# SCH_SEGEMENTOS_MINUTERO_1.net
KiCad netlist of a schematic drawn in Altium Designer
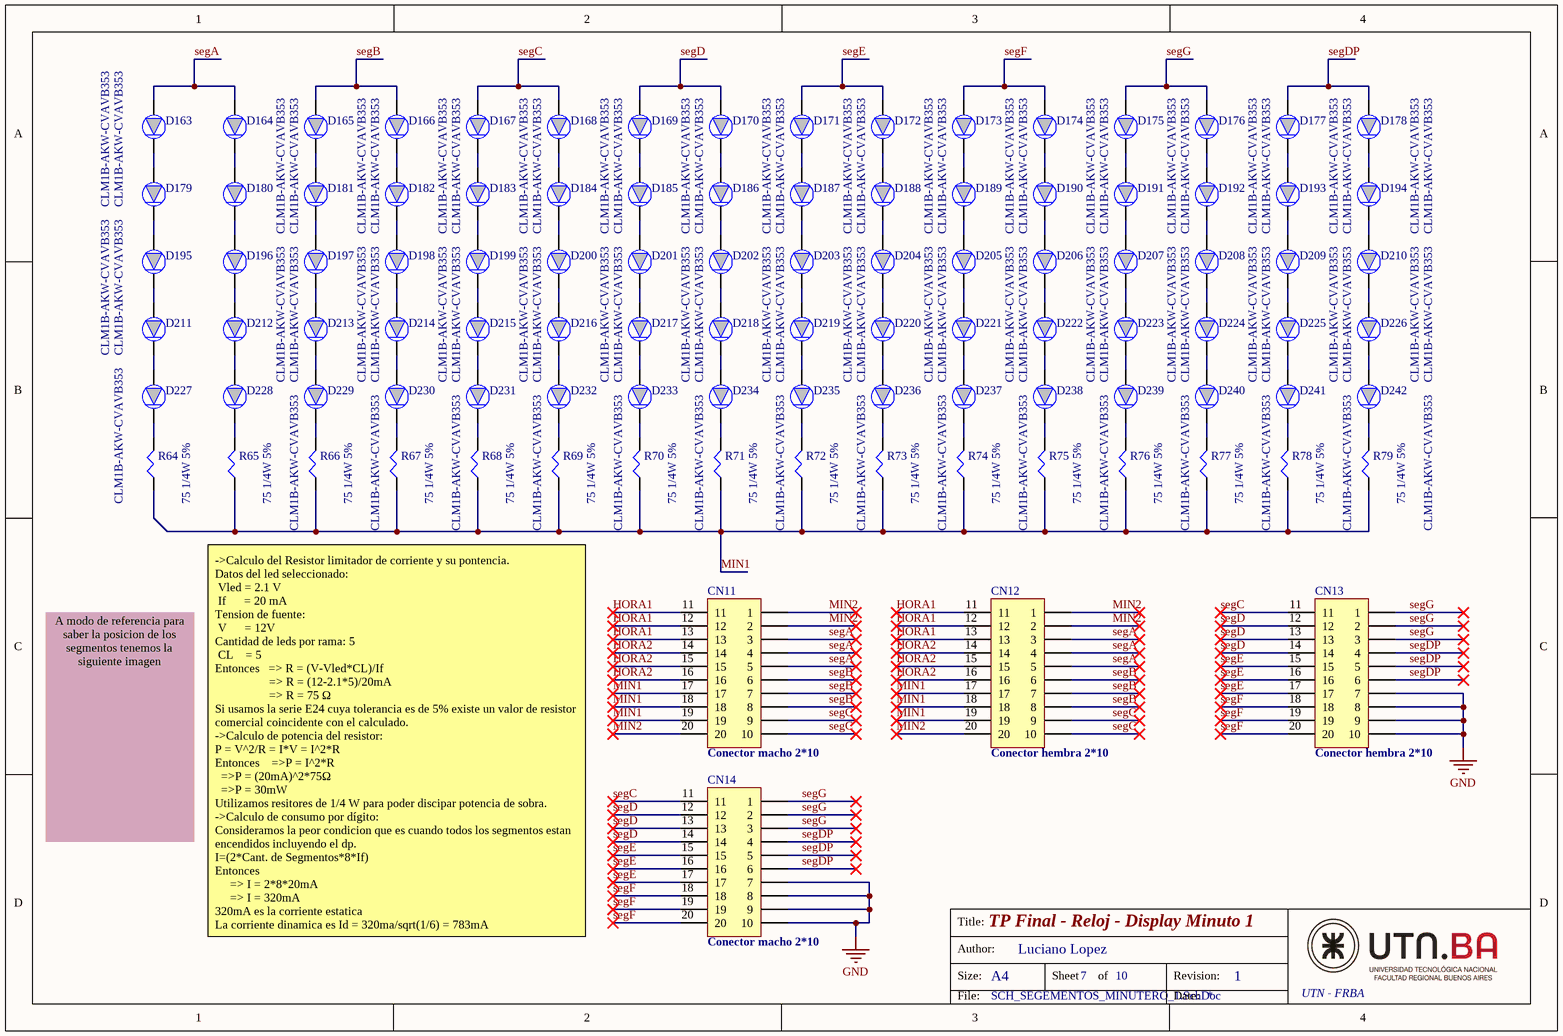
[diagram p0: SCH_SEGEMENTOS_MINUTERO_1.SchDoc]

(export (version "E")
  (design (tool "Eeschema 10.0.6"))
  (components
    (comp (ref "CN11")
      (value "Conector macho 2*10")
      (description "Connector Generic 10 Vias")
      (libsource (lib "SCH_LIB") (part "CONN_2x10P"))
    )
    (comp (ref "CN12")
      (value "Conector hembra 2*10")
      (description "Connector Generic 10 Vias")
      (libsource (lib "SCH_LIB") (part "CONN_2x10P"))
    )
    (comp (ref "CN13")
      (value "Conector hembra 2*10")
      (description "Connector Generic 10 Vias")
      (libsource (lib "SCH_LIB") (part "CONN_2x10P"))
    )
    (comp (ref "CN14")
      (value "Conector macho 2*10")
      (description "Connector Generic 10 Vias")
      (libsource (lib "SCH_LIB") (part "CONN_2x10P"))
    )
    (comp (ref "D163")
      (value "CLM1B-AKW-CVAVB353")
      (footprint "PLCC2_LED")
      (libsource (lib "SCH_LIB") (part "LED_DIODE"))
    )
    (comp (ref "D164")
      (value "CLM1B-AKW-CVAVB353")
      (footprint "PLCC2_LED")
      (libsource (lib "SCH_LIB") (part "LED_DIODE"))
    )
    (comp (ref "D165")
      (value "CLM1B-AKW-CVAVB353")
      (footprint "PLCC2_LED")
      (libsource (lib "SCH_LIB") (part "LED_DIODE"))
    )
    (comp (ref "D166")
      (value "CLM1B-AKW-CVAVB353")
      (footprint "PLCC2_LED")
      (libsource (lib "SCH_LIB") (part "LED_DIODE"))
    )
    (comp (ref "D167")
      (value "CLM1B-AKW-CVAVB353")
      (footprint "PLCC2_LED")
      (libsource (lib "SCH_LIB") (part "LED_DIODE"))
    )
    (comp (ref "D168")
      (value "CLM1B-AKW-CVAVB353")
      (footprint "PLCC2_LED")
      (libsource (lib "SCH_LIB") (part "LED_DIODE"))
    )
    (comp (ref "D169")
      (value "CLM1B-AKW-CVAVB353")
      (footprint "PLCC2_LED")
      (libsource (lib "SCH_LIB") (part "LED_DIODE"))
    )
    (comp (ref "D170")
      (value "CLM1B-AKW-CVAVB353")
      (footprint "PLCC2_LED")
      (libsource (lib "SCH_LIB") (part "LED_DIODE"))
    )
    (comp (ref "D171")
      (value "CLM1B-AKW-CVAVB353")
      (footprint "PLCC2_LED")
      (libsource (lib "SCH_LIB") (part "LED_DIODE"))
    )
    (comp (ref "D172")
      (value "CLM1B-AKW-CVAVB353")
      (footprint "PLCC2_LED")
      (libsource (lib "SCH_LIB") (part "LED_DIODE"))
    )
    (comp (ref "D173")
      (value "CLM1B-AKW-CVAVB353")
      (footprint "PLCC2_LED")
      (libsource (lib "SCH_LIB") (part "LED_DIODE"))
    )
    (comp (ref "D174")
      (value "CLM1B-AKW-CVAVB353")
      (footprint "PLCC2_LED")
      (libsource (lib "SCH_LIB") (part "LED_DIODE"))
    )
    (comp (ref "D175")
      (value "CLM1B-AKW-CVAVB353")
      (footprint "PLCC2_LED")
      (libsource (lib "SCH_LIB") (part "LED_DIODE"))
    )
    (comp (ref "D176")
      (value "CLM1B-AKW-CVAVB353")
      (footprint "PLCC2_LED")
      (libsource (lib "SCH_LIB") (part "LED_DIODE"))
    )
    (comp (ref "D177")
      (value "CLM1B-AKW-CVAVB353")
      (footprint "PLCC2_LED")
      (libsource (lib "SCH_LIB") (part "LED_DIODE"))
    )
    (comp (ref "D178")
      (value "CLM1B-AKW-CVAVB353")
      (footprint "PLCC2_LED")
      (libsource (lib "SCH_LIB") (part "LED_DIODE"))
    )
    (comp (ref "D179")
      (value "CLM1B-AKW-CVAVB353")
      (footprint "PLCC2_LED")
      (libsource (lib "SCH_LIB") (part "LED_DIODE"))
    )
    (comp (ref "D180")
      (value "CLM1B-AKW-CVAVB353")
      (footprint "PLCC2_LED")
      (libsource (lib "SCH_LIB") (part "LED_DIODE"))
    )
    (comp (ref "D181")
      (value "CLM1B-AKW-CVAVB353")
      (footprint "PLCC2_LED")
      (libsource (lib "SCH_LIB") (part "LED_DIODE"))
    )
    (comp (ref "D182")
      (value "CLM1B-AKW-CVAVB353")
      (footprint "PLCC2_LED")
      (libsource (lib "SCH_LIB") (part "LED_DIODE"))
    )
    (comp (ref "D183")
      (value "CLM1B-AKW-CVAVB353")
      (footprint "PLCC2_LED")
      (libsource (lib "SCH_LIB") (part "LED_DIODE"))
    )
    (comp (ref "D184")
      (value "CLM1B-AKW-CVAVB353")
      (footprint "PLCC2_LED")
      (libsource (lib "SCH_LIB") (part "LED_DIODE"))
    )
    (comp (ref "D185")
      (value "CLM1B-AKW-CVAVB353")
      (footprint "PLCC2_LED")
      (libsource (lib "SCH_LIB") (part "LED_DIODE"))
    )
    (comp (ref "D186")
      (value "CLM1B-AKW-CVAVB353")
      (footprint "PLCC2_LED")
      (libsource (lib "SCH_LIB") (part "LED_DIODE"))
    )
    (comp (ref "D187")
      (value "CLM1B-AKW-CVAVB353")
      (footprint "PLCC2_LED")
      (libsource (lib "SCH_LIB") (part "LED_DIODE"))
    )
    (comp (ref "D188")
      (value "CLM1B-AKW-CVAVB353")
      (footprint "PLCC2_LED")
      (libsource (lib "SCH_LIB") (part "LED_DIODE"))
    )
    (comp (ref "D189")
      (value "CLM1B-AKW-CVAVB353")
      (footprint "PLCC2_LED")
      (libsource (lib "SCH_LIB") (part "LED_DIODE"))
    )
    (comp (ref "D190")
      (value "CLM1B-AKW-CVAVB353")
      (footprint "PLCC2_LED")
      (libsource (lib "SCH_LIB") (part "LED_DIODE"))
    )
    (comp (ref "D191")
      (value "CLM1B-AKW-CVAVB353")
      (footprint "PLCC2_LED")
      (libsource (lib "SCH_LIB") (part "LED_DIODE"))
    )
    (comp (ref "D192")
      (value "CLM1B-AKW-CVAVB353")
      (footprint "PLCC2_LED")
      (libsource (lib "SCH_LIB") (part "LED_DIODE"))
    )
    (comp (ref "D193")
      (value "CLM1B-AKW-CVAVB353")
      (footprint "PLCC2_LED")
      (libsource (lib "SCH_LIB") (part "LED_DIODE"))
    )
    (comp (ref "D194")
      (value "CLM1B-AKW-CVAVB353")
      (footprint "PLCC2_LED")
      (libsource (lib "SCH_LIB") (part "LED_DIODE"))
    )
    (comp (ref "D195")
      (value "CLM1B-AKW-CVAVB353")
      (footprint "PLCC2_LED")
      (libsource (lib "SCH_LIB") (part "LED_DIODE"))
    )
    (comp (ref "D196")
      (value "CLM1B-AKW-CVAVB353")
      (footprint "PLCC2_LED")
      (libsource (lib "SCH_LIB") (part "LED_DIODE"))
    )
    (comp (ref "D197")
      (value "CLM1B-AKW-CVAVB353")
      (footprint "PLCC2_LED")
      (libsource (lib "SCH_LIB") (part "LED_DIODE"))
    )
    (comp (ref "D198")
      (value "CLM1B-AKW-CVAVB353")
      (footprint "PLCC2_LED")
      (libsource (lib "SCH_LIB") (part "LED_DIODE"))
    )
    (comp (ref "D199")
      (value "CLM1B-AKW-CVAVB353")
      (footprint "PLCC2_LED")
      (libsource (lib "SCH_LIB") (part "LED_DIODE"))
    )
    (comp (ref "D200")
      (value "CLM1B-AKW-CVAVB353")
      (footprint "PLCC2_LED")
      (libsource (lib "SCH_LIB") (part "LED_DIODE"))
    )
    (comp (ref "D201")
      (value "CLM1B-AKW-CVAVB353")
      (footprint "PLCC2_LED")
      (libsource (lib "SCH_LIB") (part "LED_DIODE"))
    )
    (comp (ref "D202")
      (value "CLM1B-AKW-CVAVB353")
      (footprint "PLCC2_LED")
      (libsource (lib "SCH_LIB") (part "LED_DIODE"))
    )
    (comp (ref "D203")
      (value "CLM1B-AKW-CVAVB353")
      (footprint "PLCC2_LED")
      (libsource (lib "SCH_LIB") (part "LED_DIODE"))
    )
    (comp (ref "D204")
      (value "CLM1B-AKW-CVAVB353")
      (footprint "PLCC2_LED")
      (libsource (lib "SCH_LIB") (part "LED_DIODE"))
    )
    (comp (ref "D205")
      (value "CLM1B-AKW-CVAVB353")
      (footprint "PLCC2_LED")
      (libsource (lib "SCH_LIB") (part "LED_DIODE"))
    )
    (comp (ref "D206")
      (value "CLM1B-AKW-CVAVB353")
      (footprint "PLCC2_LED")
      (libsource (lib "SCH_LIB") (part "LED_DIODE"))
    )
    (comp (ref "D207")
      (value "CLM1B-AKW-CVAVB353")
      (footprint "PLCC2_LED")
      (libsource (lib "SCH_LIB") (part "LED_DIODE"))
    )
    (comp (ref "D208")
      (value "CLM1B-AKW-CVAVB353")
      (footprint "PLCC2_LED")
      (libsource (lib "SCH_LIB") (part "LED_DIODE"))
    )
    (comp (ref "D209")
      (value "CLM1B-AKW-CVAVB353")
      (footprint "PLCC2_LED")
      (libsource (lib "SCH_LIB") (part "LED_DIODE"))
    )
    (comp (ref "D210")
      (value "CLM1B-AKW-CVAVB353")
      (footprint "PLCC2_LED")
      (libsource (lib "SCH_LIB") (part "LED_DIODE"))
    )
    (comp (ref "D211")
      (value "CLM1B-AKW-CVAVB353")
      (footprint "PLCC2_LED")
      (libsource (lib "SCH_LIB") (part "LED_DIODE"))
    )
    (comp (ref "D212")
      (value "CLM1B-AKW-CVAVB353")
      (footprint "PLCC2_LED")
      (libsource (lib "SCH_LIB") (part "LED_DIODE"))
    )
    (comp (ref "D213")
      (value "CLM1B-AKW-CVAVB353")
      (footprint "PLCC2_LED")
      (libsource (lib "SCH_LIB") (part "LED_DIODE"))
    )
    (comp (ref "D214")
      (value "CLM1B-AKW-CVAVB353")
      (footprint "PLCC2_LED")
      (libsource (lib "SCH_LIB") (part "LED_DIODE"))
    )
    (comp (ref "D215")
      (value "CLM1B-AKW-CVAVB353")
      (footprint "PLCC2_LED")
      (libsource (lib "SCH_LIB") (part "LED_DIODE"))
    )
    (comp (ref "D216")
      (value "CLM1B-AKW-CVAVB353")
      (footprint "PLCC2_LED")
      (libsource (lib "SCH_LIB") (part "LED_DIODE"))
    )
    (comp (ref "D217")
      (value "CLM1B-AKW-CVAVB353")
      (footprint "PLCC2_LED")
      (libsource (lib "SCH_LIB") (part "LED_DIODE"))
    )
    (comp (ref "D218")
      (value "CLM1B-AKW-CVAVB353")
      (footprint "PLCC2_LED")
      (libsource (lib "SCH_LIB") (part "LED_DIODE"))
    )
    (comp (ref "D219")
      (value "CLM1B-AKW-CVAVB353")
      (footprint "PLCC2_LED")
      (libsource (lib "SCH_LIB") (part "LED_DIODE"))
    )
    (comp (ref "D220")
      (value "CLM1B-AKW-CVAVB353")
      (footprint "PLCC2_LED")
      (libsource (lib "SCH_LIB") (part "LED_DIODE"))
    )
    (comp (ref "D221")
      (value "CLM1B-AKW-CVAVB353")
      (footprint "PLCC2_LED")
      (libsource (lib "SCH_LIB") (part "LED_DIODE"))
    )
    (comp (ref "D222")
      (value "CLM1B-AKW-CVAVB353")
      (footprint "PLCC2_LED")
      (libsource (lib "SCH_LIB") (part "LED_DIODE"))
    )
    (comp (ref "D223")
      (value "CLM1B-AKW-CVAVB353")
      (footprint "PLCC2_LED")
      (libsource (lib "SCH_LIB") (part "LED_DIODE"))
    )
    (comp (ref "D224")
      (value "CLM1B-AKW-CVAVB353")
      (footprint "PLCC2_LED")
      (libsource (lib "SCH_LIB") (part "LED_DIODE"))
    )
    (comp (ref "D225")
      (value "CLM1B-AKW-CVAVB353")
      (footprint "PLCC2_LED")
      (libsource (lib "SCH_LIB") (part "LED_DIODE"))
    )
    (comp (ref "D226")
      (value "CLM1B-AKW-CVAVB353")
      (footprint "PLCC2_LED")
      (libsource (lib "SCH_LIB") (part "LED_DIODE"))
    )
    (comp (ref "D227")
      (value "CLM1B-AKW-CVAVB353")
      (footprint "PLCC2_LED")
      (libsource (lib "SCH_LIB") (part "LED_DIODE"))
    )
    (comp (ref "D228")
      (value "CLM1B-AKW-CVAVB353")
      (footprint "PLCC2_LED")
      (libsource (lib "SCH_LIB") (part "LED_DIODE"))
    )
    (comp (ref "D229")
      (value "CLM1B-AKW-CVAVB353")
      (footprint "PLCC2_LED")
      (libsource (lib "SCH_LIB") (part "LED_DIODE"))
    )
    (comp (ref "D230")
      (value "CLM1B-AKW-CVAVB353")
      (footprint "PLCC2_LED")
      (libsource (lib "SCH_LIB") (part "LED_DIODE"))
    )
    (comp (ref "D231")
      (value "CLM1B-AKW-CVAVB353")
      (footprint "PLCC2_LED")
      (libsource (lib "SCH_LIB") (part "LED_DIODE"))
    )
    (comp (ref "D232")
      (value "CLM1B-AKW-CVAVB353")
      (footprint "PLCC2_LED")
      (libsource (lib "SCH_LIB") (part "LED_DIODE"))
    )
    (comp (ref "D233")
      (value "CLM1B-AKW-CVAVB353")
      (footprint "PLCC2_LED")
      (libsource (lib "SCH_LIB") (part "LED_DIODE"))
    )
    (comp (ref "D234")
      (value "CLM1B-AKW-CVAVB353")
      (footprint "PLCC2_LED")
      (libsource (lib "SCH_LIB") (part "LED_DIODE"))
    )
    (comp (ref "D235")
      (value "CLM1B-AKW-CVAVB353")
      (footprint "PLCC2_LED")
      (libsource (lib "SCH_LIB") (part "LED_DIODE"))
    )
    (comp (ref "D236")
      (value "CLM1B-AKW-CVAVB353")
      (footprint "PLCC2_LED")
      (libsource (lib "SCH_LIB") (part "LED_DIODE"))
    )
    (comp (ref "D237")
      (value "CLM1B-AKW-CVAVB353")
      (footprint "PLCC2_LED")
      (libsource (lib "SCH_LIB") (part "LED_DIODE"))
    )
    (comp (ref "D238")
      (value "CLM1B-AKW-CVAVB353")
      (footprint "PLCC2_LED")
      (libsource (lib "SCH_LIB") (part "LED_DIODE"))
    )
    (comp (ref "D239")
      (value "CLM1B-AKW-CVAVB353")
      (footprint "PLCC2_LED")
      (libsource (lib "SCH_LIB") (part "LED_DIODE"))
    )
    (comp (ref "D240")
      (value "CLM1B-AKW-CVAVB353")
      (footprint "PLCC2_LED")
      (libsource (lib "SCH_LIB") (part "LED_DIODE"))
    )
    (comp (ref "D241")
      (value "CLM1B-AKW-CVAVB353")
      (footprint "PLCC2_LED")
      (libsource (lib "SCH_LIB") (part "LED_DIODE"))
    )
    (comp (ref "D242")
      (value "CLM1B-AKW-CVAVB353")
      (footprint "PLCC2_LED")
      (libsource (lib "SCH_LIB") (part "LED_DIODE"))
    )
    (comp (ref "R64") (value "75 1/4W 5%") (footprint "R_0805") (libsource (lib "SCH_LIB") (part "Resistor")))
    (comp (ref "R65") (value "75 1/4W 5%") (footprint "R_0805") (libsource (lib "SCH_LIB") (part "Resistor")))
    (comp (ref "R66") (value "75 1/4W 5%") (footprint "R_0805") (libsource (lib "SCH_LIB") (part "Resistor")))
    (comp (ref "R67") (value "75 1/4W 5%") (footprint "R_0805") (libsource (lib "SCH_LIB") (part "Resistor")))
    (comp (ref "R68") (value "75 1/4W 5%") (footprint "R_0805") (libsource (lib "SCH_LIB") (part "Resistor")))
    (comp (ref "R69") (value "75 1/4W 5%") (footprint "R_0805") (libsource (lib "SCH_LIB") (part "Resistor")))
    (comp (ref "R70") (value "75 1/4W 5%") (footprint "R_0805") (libsource (lib "SCH_LIB") (part "Resistor")))
    (comp (ref "R71") (value "75 1/4W 5%") (footprint "R_0805") (libsource (lib "SCH_LIB") (part "Resistor")))
    (comp (ref "R72") (value "75 1/4W 5%") (footprint "R_0805") (libsource (lib "SCH_LIB") (part "Resistor")))
    (comp (ref "R73") (value "75 1/4W 5%") (footprint "R_0805") (libsource (lib "SCH_LIB") (part "Resistor")))
    (comp (ref "R74") (value "75 1/4W 5%") (footprint "R_0805") (libsource (lib "SCH_LIB") (part "Resistor")))
    (comp (ref "R75") (value "75 1/4W 5%") (footprint "R_0805") (libsource (lib "SCH_LIB") (part "Resistor")))
    (comp (ref "R76") (value "75 1/4W 5%") (footprint "R_0805") (libsource (lib "SCH_LIB") (part "Resistor")))
    (comp (ref "R77") (value "75 1/4W 5%") (footprint "R_0805") (libsource (lib "SCH_LIB") (part "Resistor")))
    (comp (ref "R78") (value "75 1/4W 5%") (footprint "R_0805") (libsource (lib "SCH_LIB") (part "Resistor")))
    (comp (ref "R79") (value "75 1/4W 5%") (footprint "R_0805") (libsource (lib "SCH_LIB") (part "Resistor")))
  )
  (nets
    (net (code "1") (name "/HORA1") (class "Default")
      (node (ref "CN11") (pin "11") (pinfunction "11_11") (pintype "passive"))
      (node (ref "CN11") (pin "12") (pinfunction "12_12") (pintype "passive"))
      (node (ref "CN11") (pin "13") (pinfunction "13_13") (pintype "passive"))
      (node (ref "CN12") (pin "11") (pinfunction "11_11") (pintype "passive"))
      (node (ref "CN12") (pin "12") (pinfunction "12_12") (pintype "passive"))
      (node (ref "CN12") (pin "13") (pinfunction "13_13") (pintype "passive"))
    )
    (net (code "2") (name "/HORA2") (class "Default")
      (node (ref "CN11") (pin "14") (pinfunction "14_14") (pintype "passive"))
      (node (ref "CN11") (pin "15") (pinfunction "15_15") (pintype "passive"))
      (node (ref "CN11") (pin "16") (pinfunction "16_16") (pintype "passive"))
      (node (ref "CN12") (pin "14") (pinfunction "14_14") (pintype "passive"))
      (node (ref "CN12") (pin "15") (pinfunction "15_15") (pintype "passive"))
      (node (ref "CN12") (pin "16") (pinfunction "16_16") (pintype "passive"))
    )
    (net (code "3") (name "/MIN1") (class "Default")
      (node (ref "CN11") (pin "17") (pinfunction "17_17") (pintype "passive"))
      (node (ref "CN11") (pin "18") (pinfunction "18_18") (pintype "passive"))
      (node (ref "CN11") (pin "19") (pinfunction "19_19") (pintype "passive"))
      (node (ref "CN12") (pin "17") (pinfunction "17_17") (pintype "passive"))
      (node (ref "CN12") (pin "18") (pinfunction "18_18") (pintype "passive"))
      (node (ref "CN12") (pin "19") (pinfunction "19_19") (pintype "passive"))
      (node (ref "R64") (pin "47") (pinfunction "47_47") (pintype "passive"))
      (node (ref "R65") (pin "47") (pinfunction "47_47") (pintype "passive"))
      (node (ref "R66") (pin "47") (pinfunction "47_47") (pintype "passive"))
      (node (ref "R67") (pin "47") (pinfunction "47_47") (pintype "passive"))
      (node (ref "R68") (pin "47") (pinfunction "47_47") (pintype "passive"))
      (node (ref "R69") (pin "47") (pinfunction "47_47") (pintype "passive"))
      (node (ref "R70") (pin "47") (pinfunction "47_47") (pintype "passive"))
      (node (ref "R71") (pin "47") (pinfunction "47_47") (pintype "passive"))
      (node (ref "R72") (pin "47") (pinfunction "47_47") (pintype "passive"))
      (node (ref "R73") (pin "47") (pinfunction "47_47") (pintype "passive"))
      (node (ref "R74") (pin "47") (pinfunction "47_47") (pintype "passive"))
      (node (ref "R75") (pin "47") (pinfunction "47_47") (pintype "passive"))
      (node (ref "R76") (pin "47") (pinfunction "47_47") (pintype "passive"))
      (node (ref "R77") (pin "47") (pinfunction "47_47") (pintype "passive"))
      (node (ref "R78") (pin "47") (pinfunction "47_47") (pintype "passive"))
      (node (ref "R79") (pin "47") (pinfunction "47_47") (pintype "passive"))
    )
    (net (code "4") (name "/MIN2") (class "Default")
      (node (ref "CN11") (pin "1") (pinfunction "1_1") (pintype "passive"))
      (node (ref "CN11") (pin "2") (pinfunction "2_2") (pintype "passive"))
      (node (ref "CN11") (pin "20") (pinfunction "20_20") (pintype "passive"))
      (node (ref "CN12") (pin "1") (pinfunction "1_1") (pintype "passive"))
      (node (ref "CN12") (pin "2") (pinfunction "2_2") (pintype "passive"))
      (node (ref "CN12") (pin "20") (pinfunction "20_20") (pintype "passive"))
    )
    (net (code "5") (name "/segA") (class "Default")
      (node (ref "CN11") (pin "3") (pinfunction "3_3") (pintype "passive"))
      (node (ref "CN11") (pin "4") (pinfunction "4_4") (pintype "passive"))
      (node (ref "CN11") (pin "5") (pinfunction "5_5") (pintype "passive"))
      (node (ref "CN12") (pin "3") (pinfunction "3_3") (pintype "passive"))
      (node (ref "CN12") (pin "4") (pinfunction "4_4") (pintype "passive"))
      (node (ref "CN12") (pin "5") (pinfunction "5_5") (pintype "passive"))
      (node (ref "D163") (pin "12") (pinfunction "12_12") (pintype "passive"))
      (node (ref "D164") (pin "12") (pinfunction "12_12") (pintype "passive"))
    )
    (net (code "6") (name "/segB") (class "Default")
      (node (ref "CN11") (pin "6") (pinfunction "6_6") (pintype "passive"))
      (node (ref "CN11") (pin "7") (pinfunction "7_7") (pintype "passive"))
      (node (ref "CN11") (pin "8") (pinfunction "8_8") (pintype "passive"))
      (node (ref "CN12") (pin "6") (pinfunction "6_6") (pintype "passive"))
      (node (ref "CN12") (pin "7") (pinfunction "7_7") (pintype "passive"))
      (node (ref "CN12") (pin "8") (pinfunction "8_8") (pintype "passive"))
      (node (ref "D165") (pin "12") (pinfunction "12_12") (pintype "passive"))
      (node (ref "D166") (pin "12") (pinfunction "12_12") (pintype "passive"))
    )
    (net (code "7") (name "/segC") (class "Default")
      (node (ref "CN11") (pin "10") (pinfunction "10_10") (pintype "passive"))
      (node (ref "CN11") (pin "9") (pinfunction "9_9") (pintype "passive"))
      (node (ref "CN12") (pin "10") (pinfunction "10_10") (pintype "passive"))
      (node (ref "CN12") (pin "9") (pinfunction "9_9") (pintype "passive"))
      (node (ref "CN13") (pin "11") (pinfunction "11_11") (pintype "passive"))
      (node (ref "CN14") (pin "11") (pinfunction "11_11") (pintype "passive"))
      (node (ref "D167") (pin "12") (pinfunction "12_12") (pintype "passive"))
      (node (ref "D168") (pin "12") (pinfunction "12_12") (pintype "passive"))
    )
    (net (code "8") (name "/segD") (class "Default")
      (node (ref "CN13") (pin "12") (pinfunction "12_12") (pintype "passive"))
      (node (ref "CN13") (pin "13") (pinfunction "13_13") (pintype "passive"))
      (node (ref "CN13") (pin "14") (pinfunction "14_14") (pintype "passive"))
      (node (ref "CN14") (pin "12") (pinfunction "12_12") (pintype "passive"))
      (node (ref "CN14") (pin "13") (pinfunction "13_13") (pintype "passive"))
      (node (ref "CN14") (pin "14") (pinfunction "14_14") (pintype "passive"))
      (node (ref "D169") (pin "12") (pinfunction "12_12") (pintype "passive"))
      (node (ref "D170") (pin "12") (pinfunction "12_12") (pintype "passive"))
    )
    (net (code "9") (name "/segDP") (class "Default")
      (node (ref "CN13") (pin "4") (pinfunction "4_4") (pintype "passive"))
      (node (ref "CN13") (pin "5") (pinfunction "5_5") (pintype "passive"))
      (node (ref "CN13") (pin "6") (pinfunction "6_6") (pintype "passive"))
      (node (ref "CN14") (pin "4") (pinfunction "4_4") (pintype "passive"))
      (node (ref "CN14") (pin "5") (pinfunction "5_5") (pintype "passive"))
      (node (ref "CN14") (pin "6") (pinfunction "6_6") (pintype "passive"))
      (node (ref "D177") (pin "12") (pinfunction "12_12") (pintype "passive"))
      (node (ref "D178") (pin "12") (pinfunction "12_12") (pintype "passive"))
    )
    (net (code "10") (name "/segE") (class "Default")
      (node (ref "CN13") (pin "15") (pinfunction "15_15") (pintype "passive"))
      (node (ref "CN13") (pin "16") (pinfunction "16_16") (pintype "passive"))
      (node (ref "CN13") (pin "17") (pinfunction "17_17") (pintype "passive"))
      (node (ref "CN14") (pin "15") (pinfunction "15_15") (pintype "passive"))
      (node (ref "CN14") (pin "16") (pinfunction "16_16") (pintype "passive"))
      (node (ref "CN14") (pin "17") (pinfunction "17_17") (pintype "passive"))
      (node (ref "D171") (pin "12") (pinfunction "12_12") (pintype "passive"))
      (node (ref "D172") (pin "12") (pinfunction "12_12") (pintype "passive"))
    )
    (net (code "11") (name "/segF") (class "Default")
      (node (ref "CN13") (pin "18") (pinfunction "18_18") (pintype "passive"))
      (node (ref "CN13") (pin "19") (pinfunction "19_19") (pintype "passive"))
      (node (ref "CN13") (pin "20") (pinfunction "20_20") (pintype "passive"))
      (node (ref "CN14") (pin "18") (pinfunction "18_18") (pintype "passive"))
      (node (ref "CN14") (pin "19") (pinfunction "19_19") (pintype "passive"))
      (node (ref "CN14") (pin "20") (pinfunction "20_20") (pintype "passive"))
      (node (ref "D173") (pin "12") (pinfunction "12_12") (pintype "passive"))
      (node (ref "D174") (pin "12") (pinfunction "12_12") (pintype "passive"))
    )
    (net (code "12") (name "/segG") (class "Default")
      (node (ref "CN13") (pin "1") (pinfunction "1_1") (pintype "passive"))
      (node (ref "CN13") (pin "2") (pinfunction "2_2") (pintype "passive"))
      (node (ref "CN13") (pin "3") (pinfunction "3_3") (pintype "passive"))
      (node (ref "CN14") (pin "1") (pinfunction "1_1") (pintype "passive"))
      (node (ref "CN14") (pin "2") (pinfunction "2_2") (pintype "passive"))
      (node (ref "CN14") (pin "3") (pinfunction "3_3") (pintype "passive"))
      (node (ref "D175") (pin "12") (pinfunction "12_12") (pintype "passive"))
      (node (ref "D176") (pin "12") (pinfunction "12_12") (pintype "passive"))
    )
    (net (code "13") (name "GND") (class "Default")
      (node (ref "CN13") (pin "10") (pinfunction "10_10") (pintype "passive"))
      (node (ref "CN13") (pin "7") (pinfunction "7_7") (pintype "passive"))
      (node (ref "CN13") (pin "8") (pinfunction "8_8") (pintype "passive"))
      (node (ref "CN13") (pin "9") (pinfunction "9_9") (pintype "passive"))
      (node (ref "CN14") (pin "10") (pinfunction "10_10") (pintype "passive"))
      (node (ref "CN14") (pin "7") (pinfunction "7_7") (pintype "passive"))
      (node (ref "CN14") (pin "8") (pinfunction "8_8") (pintype "passive"))
      (node (ref "CN14") (pin "9") (pinfunction "9_9") (pintype "passive"))
    )
    (net (code "14") (name "Net-(D163-Pad11)") (class "Default")
      (node (ref "D163") (pin "11") (pinfunction "11_11") (pintype "passive"))
      (node (ref "D179") (pin "12") (pinfunction "12_12") (pintype "passive"))
    )
    (net (code "15") (name "Net-(D164-Pad11)") (class "Default")
      (node (ref "D164") (pin "11") (pinfunction "11_11") (pintype "passive"))
      (node (ref "D180") (pin "12") (pinfunction "12_12") (pintype "passive"))
    )
    (net (code "16") (name "Net-(D165-Pad11)") (class "Default")
      (node (ref "D165") (pin "11") (pinfunction "11_11") (pintype "passive"))
      (node (ref "D181") (pin "12") (pinfunction "12_12") (pintype "passive"))
    )
    (net (code "17") (name "Net-(D166-Pad11)") (class "Default")
      (node (ref "D166") (pin "11") (pinfunction "11_11") (pintype "passive"))
      (node (ref "D182") (pin "12") (pinfunction "12_12") (pintype "passive"))
    )
    (net (code "18") (name "Net-(D167-Pad11)") (class "Default")
      (node (ref "D167") (pin "11") (pinfunction "11_11") (pintype "passive"))
      (node (ref "D183") (pin "12") (pinfunction "12_12") (pintype "passive"))
    )
    (net (code "19") (name "Net-(D168-Pad11)") (class "Default")
      (node (ref "D168") (pin "11") (pinfunction "11_11") (pintype "passive"))
      (node (ref "D184") (pin "12") (pinfunction "12_12") (pintype "passive"))
    )
    (net (code "20") (name "Net-(D169-Pad11)") (class "Default")
      (node (ref "D169") (pin "11") (pinfunction "11_11") (pintype "passive"))
      (node (ref "D185") (pin "12") (pinfunction "12_12") (pintype "passive"))
    )
    (net (code "21") (name "Net-(D170-Pad11)") (class "Default")
      (node (ref "D170") (pin "11") (pinfunction "11_11") (pintype "passive"))
      (node (ref "D186") (pin "12") (pinfunction "12_12") (pintype "passive"))
    )
    (net (code "22") (name "Net-(D171-Pad11)") (class "Default")
      (node (ref "D171") (pin "11") (pinfunction "11_11") (pintype "passive"))
      (node (ref "D187") (pin "12") (pinfunction "12_12") (pintype "passive"))
    )
    (net (code "23") (name "Net-(D172-Pad11)") (class "Default")
      (node (ref "D172") (pin "11") (pinfunction "11_11") (pintype "passive"))
      (node (ref "D188") (pin "12") (pinfunction "12_12") (pintype "passive"))
    )
    (net (code "24") (name "Net-(D173-Pad11)") (class "Default")
      (node (ref "D173") (pin "11") (pinfunction "11_11") (pintype "passive"))
      (node (ref "D189") (pin "12") (pinfunction "12_12") (pintype "passive"))
    )
    (net (code "25") (name "Net-(D174-Pad11)") (class "Default")
      (node (ref "D174") (pin "11") (pinfunction "11_11") (pintype "passive"))
      (node (ref "D190") (pin "12") (pinfunction "12_12") (pintype "passive"))
    )
    (net (code "26") (name "Net-(D175-Pad11)") (class "Default")
      (node (ref "D175") (pin "11") (pinfunction "11_11") (pintype "passive"))
      (node (ref "D191") (pin "12") (pinfunction "12_12") (pintype "passive"))
    )
    (net (code "27") (name "Net-(D176-Pad11)") (class "Default")
      (node (ref "D176") (pin "11") (pinfunction "11_11") (pintype "passive"))
      (node (ref "D192") (pin "12") (pinfunction "12_12") (pintype "passive"))
    )
    (net (code "28") (name "Net-(D177-Pad11)") (class "Default")
      (node (ref "D177") (pin "11") (pinfunction "11_11") (pintype "passive"))
      (node (ref "D193") (pin "12") (pinfunction "12_12") (pintype "passive"))
    )
    (net (code "29") (name "Net-(D178-Pad11)") (class "Default")
      (node (ref "D178") (pin "11") (pinfunction "11_11") (pintype "passive"))
      (node (ref "D194") (pin "12") (pinfunction "12_12") (pintype "passive"))
    )
    (net (code "30") (name "Net-(D179-Pad11)") (class "Default")
      (node (ref "D179") (pin "11") (pinfunction "11_11") (pintype "passive"))
      (node (ref "D195") (pin "12") (pinfunction "12_12") (pintype "passive"))
    )
    (net (code "31") (name "Net-(D180-Pad11)") (class "Default")
      (node (ref "D180") (pin "11") (pinfunction "11_11") (pintype "passive"))
      (node (ref "D196") (pin "12") (pinfunction "12_12") (pintype "passive"))
    )
    (net (code "32") (name "Net-(D181-Pad11)") (class "Default")
      (node (ref "D181") (pin "11") (pinfunction "11_11") (pintype "passive"))
      (node (ref "D197") (pin "12") (pinfunction "12_12") (pintype "passive"))
    )
    (net (code "33") (name "Net-(D182-Pad11)") (class "Default")
      (node (ref "D182") (pin "11") (pinfunction "11_11") (pintype "passive"))
      (node (ref "D198") (pin "12") (pinfunction "12_12") (pintype "passive"))
    )
    (net (code "34") (name "Net-(D183-Pad11)") (class "Default")
      (node (ref "D183") (pin "11") (pinfunction "11_11") (pintype "passive"))
      (node (ref "D199") (pin "12") (pinfunction "12_12") (pintype "passive"))
    )
    (net (code "35") (name "Net-(D184-Pad11)") (class "Default")
      (node (ref "D184") (pin "11") (pinfunction "11_11") (pintype "passive"))
      (node (ref "D200") (pin "12") (pinfunction "12_12") (pintype "passive"))
    )
    (net (code "36") (name "Net-(D185-Pad11)") (class "Default")
      (node (ref "D185") (pin "11") (pinfunction "11_11") (pintype "passive"))
      (node (ref "D201") (pin "12") (pinfunction "12_12") (pintype "passive"))
    )
    (net (code "37") (name "Net-(D186-Pad11)") (class "Default")
      (node (ref "D186") (pin "11") (pinfunction "11_11") (pintype "passive"))
      (node (ref "D202") (pin "12") (pinfunction "12_12") (pintype "passive"))
    )
    (net (code "38") (name "Net-(D187-Pad11)") (class "Default")
      (node (ref "D187") (pin "11") (pinfunction "11_11") (pintype "passive"))
      (node (ref "D203") (pin "12") (pinfunction "12_12") (pintype "passive"))
    )
    (net (code "39") (name "Net-(D188-Pad11)") (class "Default")
      (node (ref "D188") (pin "11") (pinfunction "11_11") (pintype "passive"))
      (node (ref "D204") (pin "12") (pinfunction "12_12") (pintype "passive"))
    )
    (net (code "40") (name "Net-(D189-Pad11)") (class "Default")
      (node (ref "D189") (pin "11") (pinfunction "11_11") (pintype "passive"))
      (node (ref "D205") (pin "12") (pinfunction "12_12") (pintype "passive"))
    )
    (net (code "41") (name "Net-(D190-Pad11)") (class "Default")
      (node (ref "D190") (pin "11") (pinfunction "11_11") (pintype "passive"))
      (node (ref "D206") (pin "12") (pinfunction "12_12") (pintype "passive"))
    )
    (net (code "42") (name "Net-(D191-Pad11)") (class "Default")
      (node (ref "D191") (pin "11") (pinfunction "11_11") (pintype "passive"))
      (node (ref "D207") (pin "12") (pinfunction "12_12") (pintype "passive"))
    )
    (net (code "43") (name "Net-(D192-Pad11)") (class "Default")
      (node (ref "D192") (pin "11") (pinfunction "11_11") (pintype "passive"))
      (node (ref "D208") (pin "12") (pinfunction "12_12") (pintype "passive"))
    )
    (net (code "44") (name "Net-(D193-Pad11)") (class "Default")
      (node (ref "D193") (pin "11") (pinfunction "11_11") (pintype "passive"))
      (node (ref "D209") (pin "12") (pinfunction "12_12") (pintype "passive"))
    )
    (net (code "45") (name "Net-(D194-Pad11)") (class "Default")
      (node (ref "D194") (pin "11") (pinfunction "11_11") (pintype "passive"))
      (node (ref "D210") (pin "12") (pinfunction "12_12") (pintype "passive"))
    )
    (net (code "46") (name "Net-(D195-Pad11)") (class "Default")
      (node (ref "D195") (pin "11") (pinfunction "11_11") (pintype "passive"))
      (node (ref "D211") (pin "12") (pinfunction "12_12") (pintype "passive"))
    )
    (net (code "47") (name "Net-(D196-Pad11)") (class "Default")
      (node (ref "D196") (pin "11") (pinfunction "11_11") (pintype "passive"))
      (node (ref "D212") (pin "12") (pinfunction "12_12") (pintype "passive"))
    )
    (net (code "48") (name "Net-(D197-Pad11)") (class "Default")
      (node (ref "D197") (pin "11") (pinfunction "11_11") (pintype "passive"))
      (node (ref "D213") (pin "12") (pinfunction "12_12") (pintype "passive"))
    )
    (net (code "49") (name "Net-(D198-Pad11)") (class "Default")
      (node (ref "D198") (pin "11") (pinfunction "11_11") (pintype "passive"))
      (node (ref "D214") (pin "12") (pinfunction "12_12") (pintype "passive"))
    )
    (net (code "50") (name "Net-(D199-Pad11)") (class "Default")
      (node (ref "D199") (pin "11") (pinfunction "11_11") (pintype "passive"))
      (node (ref "D215") (pin "12") (pinfunction "12_12") (pintype "passive"))
    )
    (net (code "51") (name "Net-(D200-Pad11)") (class "Default")
      (node (ref "D200") (pin "11") (pinfunction "11_11") (pintype "passive"))
      (node (ref "D216") (pin "12") (pinfunction "12_12") (pintype "passive"))
    )
    (net (code "52") (name "Net-(D201-Pad11)") (class "Default")
      (node (ref "D201") (pin "11") (pinfunction "11_11") (pintype "passive"))
      (node (ref "D217") (pin "12") (pinfunction "12_12") (pintype "passive"))
    )
    (net (code "53") (name "Net-(D202-Pad11)") (class "Default")
      (node (ref "D202") (pin "11") (pinfunction "11_11") (pintype "passive"))
      (node (ref "D218") (pin "12") (pinfunction "12_12") (pintype "passive"))
    )
    (net (code "54") (name "Net-(D203-Pad11)") (class "Default")
      (node (ref "D203") (pin "11") (pinfunction "11_11") (pintype "passive"))
      (node (ref "D219") (pin "12") (pinfunction "12_12") (pintype "passive"))
    )
    (net (code "55") (name "Net-(D204-Pad11)") (class "Default")
      (node (ref "D204") (pin "11") (pinfunction "11_11") (pintype "passive"))
      (node (ref "D220") (pin "12") (pinfunction "12_12") (pintype "passive"))
    )
    (net (code "56") (name "Net-(D205-Pad11)") (class "Default")
      (node (ref "D205") (pin "11") (pinfunction "11_11") (pintype "passive"))
      (node (ref "D221") (pin "12") (pinfunction "12_12") (pintype "passive"))
    )
    (net (code "57") (name "Net-(D206-Pad11)") (class "Default")
      (node (ref "D206") (pin "11") (pinfunction "11_11") (pintype "passive"))
      (node (ref "D222") (pin "12") (pinfunction "12_12") (pintype "passive"))
    )
    (net (code "58") (name "Net-(D207-Pad11)") (class "Default")
      (node (ref "D207") (pin "11") (pinfunction "11_11") (pintype "passive"))
      (node (ref "D223") (pin "12") (pinfunction "12_12") (pintype "passive"))
    )
    (net (code "59") (name "Net-(D208-Pad11)") (class "Default")
      (node (ref "D208") (pin "11") (pinfunction "11_11") (pintype "passive"))
      (node (ref "D224") (pin "12") (pinfunction "12_12") (pintype "passive"))
    )
    (net (code "60") (name "Net-(D209-Pad11)") (class "Default")
      (node (ref "D209") (pin "11") (pinfunction "11_11") (pintype "passive"))
      (node (ref "D225") (pin "12") (pinfunction "12_12") (pintype "passive"))
    )
    (net (code "61") (name "Net-(D210-Pad11)") (class "Default")
      (node (ref "D210") (pin "11") (pinfunction "11_11") (pintype "passive"))
      (node (ref "D226") (pin "12") (pinfunction "12_12") (pintype "passive"))
    )
    (net (code "62") (name "Net-(D211-Pad11)") (class "Default")
      (node (ref "D211") (pin "11") (pinfunction "11_11") (pintype "passive"))
      (node (ref "D227") (pin "12") (pinfunction "12_12") (pintype "passive"))
    )
    (net (code "63") (name "Net-(D212-Pad11)") (class "Default")
      (node (ref "D212") (pin "11") (pinfunction "11_11") (pintype "passive"))
      (node (ref "D228") (pin "12") (pinfunction "12_12") (pintype "passive"))
    )
    (net (code "64") (name "Net-(D213-Pad11)") (class "Default")
      (node (ref "D213") (pin "11") (pinfunction "11_11") (pintype "passive"))
      (node (ref "D229") (pin "12") (pinfunction "12_12") (pintype "passive"))
    )
    (net (code "65") (name "Net-(D214-Pad11)") (class "Default")
      (node (ref "D214") (pin "11") (pinfunction "11_11") (pintype "passive"))
      (node (ref "D230") (pin "12") (pinfunction "12_12") (pintype "passive"))
    )
    (net (code "66") (name "Net-(D215-Pad11)") (class "Default")
      (node (ref "D215") (pin "11") (pinfunction "11_11") (pintype "passive"))
      (node (ref "D231") (pin "12") (pinfunction "12_12") (pintype "passive"))
    )
    (net (code "67") (name "Net-(D216-Pad11)") (class "Default")
      (node (ref "D216") (pin "11") (pinfunction "11_11") (pintype "passive"))
      (node (ref "D232") (pin "12") (pinfunction "12_12") (pintype "passive"))
    )
    (net (code "68") (name "Net-(D217-Pad11)") (class "Default")
      (node (ref "D217") (pin "11") (pinfunction "11_11") (pintype "passive"))
      (node (ref "D233") (pin "12") (pinfunction "12_12") (pintype "passive"))
    )
    (net (code "69") (name "Net-(D218-Pad11)") (class "Default")
      (node (ref "D218") (pin "11") (pinfunction "11_11") (pintype "passive"))
      (node (ref "D234") (pin "12") (pinfunction "12_12") (pintype "passive"))
    )
    (net (code "70") (name "Net-(D219-Pad11)") (class "Default")
      (node (ref "D219") (pin "11") (pinfunction "11_11") (pintype "passive"))
      (node (ref "D235") (pin "12") (pinfunction "12_12") (pintype "passive"))
    )
    (net (code "71") (name "Net-(D220-Pad11)") (class "Default")
      (node (ref "D220") (pin "11") (pinfunction "11_11") (pintype "passive"))
      (node (ref "D236") (pin "12") (pinfunction "12_12") (pintype "passive"))
    )
    (net (code "72") (name "Net-(D221-Pad11)") (class "Default")
      (node (ref "D221") (pin "11") (pinfunction "11_11") (pintype "passive"))
      (node (ref "D237") (pin "12") (pinfunction "12_12") (pintype "passive"))
    )
    (net (code "73") (name "Net-(D222-Pad11)") (class "Default")
      (node (ref "D222") (pin "11") (pinfunction "11_11") (pintype "passive"))
      (node (ref "D238") (pin "12") (pinfunction "12_12") (pintype "passive"))
    )
    (net (code "74") (name "Net-(D223-Pad11)") (class "Default")
      (node (ref "D223") (pin "11") (pinfunction "11_11") (pintype "passive"))
      (node (ref "D239") (pin "12") (pinfunction "12_12") (pintype "passive"))
    )
    (net (code "75") (name "Net-(D224-Pad11)") (class "Default")
      (node (ref "D224") (pin "11") (pinfunction "11_11") (pintype "passive"))
      (node (ref "D240") (pin "12") (pinfunction "12_12") (pintype "passive"))
    )
    (net (code "76") (name "Net-(D225-Pad11)") (class "Default")
      (node (ref "D225") (pin "11") (pinfunction "11_11") (pintype "passive"))
      (node (ref "D241") (pin "12") (pinfunction "12_12") (pintype "passive"))
    )
    (net (code "77") (name "Net-(D226-Pad11)") (class "Default")
      (node (ref "D226") (pin "11") (pinfunction "11_11") (pintype "passive"))
      (node (ref "D242") (pin "12") (pinfunction "12_12") (pintype "passive"))
    )
    (net (code "78") (name "Net-(D227-Pad11)") (class "Default")
      (node (ref "D227") (pin "11") (pinfunction "11_11") (pintype "passive"))
      (node (ref "R64") (pin "48") (pinfunction "48_48") (pintype "passive"))
    )
    (net (code "79") (name "Net-(D228-Pad11)") (class "Default")
      (node (ref "D228") (pin "11") (pinfunction "11_11") (pintype "passive"))
      (node (ref "R65") (pin "48") (pinfunction "48_48") (pintype "passive"))
    )
    (net (code "80") (name "Net-(D229-Pad11)") (class "Default")
      (node (ref "D229") (pin "11") (pinfunction "11_11") (pintype "passive"))
      (node (ref "R66") (pin "48") (pinfunction "48_48") (pintype "passive"))
    )
    (net (code "81") (name "Net-(D230-Pad11)") (class "Default")
      (node (ref "D230") (pin "11") (pinfunction "11_11") (pintype "passive"))
      (node (ref "R67") (pin "48") (pinfunction "48_48") (pintype "passive"))
    )
    (net (code "82") (name "Net-(D231-Pad11)") (class "Default")
      (node (ref "D231") (pin "11") (pinfunction "11_11") (pintype "passive"))
      (node (ref "R68") (pin "48") (pinfunction "48_48") (pintype "passive"))
    )
    (net (code "83") (name "Net-(D232-Pad11)") (class "Default")
      (node (ref "D232") (pin "11") (pinfunction "11_11") (pintype "passive"))
      (node (ref "R69") (pin "48") (pinfunction "48_48") (pintype "passive"))
    )
    (net (code "84") (name "Net-(D233-Pad11)") (class "Default")
      (node (ref "D233") (pin "11") (pinfunction "11_11") (pintype "passive"))
      (node (ref "R70") (pin "48") (pinfunction "48_48") (pintype "passive"))
    )
    (net (code "85") (name "Net-(D234-Pad11)") (class "Default")
      (node (ref "D234") (pin "11") (pinfunction "11_11") (pintype "passive"))
      (node (ref "R71") (pin "48") (pinfunction "48_48") (pintype "passive"))
    )
    (net (code "86") (name "Net-(D235-Pad11)") (class "Default")
      (node (ref "D235") (pin "11") (pinfunction "11_11") (pintype "passive"))
      (node (ref "R72") (pin "48") (pinfunction "48_48") (pintype "passive"))
    )
    (net (code "87") (name "Net-(D236-Pad11)") (class "Default")
      (node (ref "D236") (pin "11") (pinfunction "11_11") (pintype "passive"))
      (node (ref "R73") (pin "48") (pinfunction "48_48") (pintype "passive"))
    )
    (net (code "88") (name "Net-(D237-Pad11)") (class "Default")
      (node (ref "D237") (pin "11") (pinfunction "11_11") (pintype "passive"))
      (node (ref "R74") (pin "48") (pinfunction "48_48") (pintype "passive"))
    )
    (net (code "89") (name "Net-(D238-Pad11)") (class "Default")
      (node (ref "D238") (pin "11") (pinfunction "11_11") (pintype "passive"))
      (node (ref "R75") (pin "48") (pinfunction "48_48") (pintype "passive"))
    )
    (net (code "90") (name "Net-(D239-Pad11)") (class "Default")
      (node (ref "D239") (pin "11") (pinfunction "11_11") (pintype "passive"))
      (node (ref "R76") (pin "48") (pinfunction "48_48") (pintype "passive"))
    )
    (net (code "91") (name "Net-(D240-Pad11)") (class "Default")
      (node (ref "D240") (pin "11") (pinfunction "11_11") (pintype "passive"))
      (node (ref "R77") (pin "48") (pinfunction "48_48") (pintype "passive"))
    )
    (net (code "92") (name "Net-(D241-Pad11)") (class "Default")
      (node (ref "D241") (pin "11") (pinfunction "11_11") (pintype "passive"))
      (node (ref "R78") (pin "48") (pinfunction "48_48") (pintype "passive"))
    )
    (net (code "93") (name "Net-(D242-Pad11)") (class "Default")
      (node (ref "D242") (pin "11") (pinfunction "11_11") (pintype "passive"))
      (node (ref "R79") (pin "48") (pinfunction "48_48") (pintype "passive"))
    )
  )
)
